# modbrainsv0_3.net
KiCad netlist of a schematic drawn in EAGLE
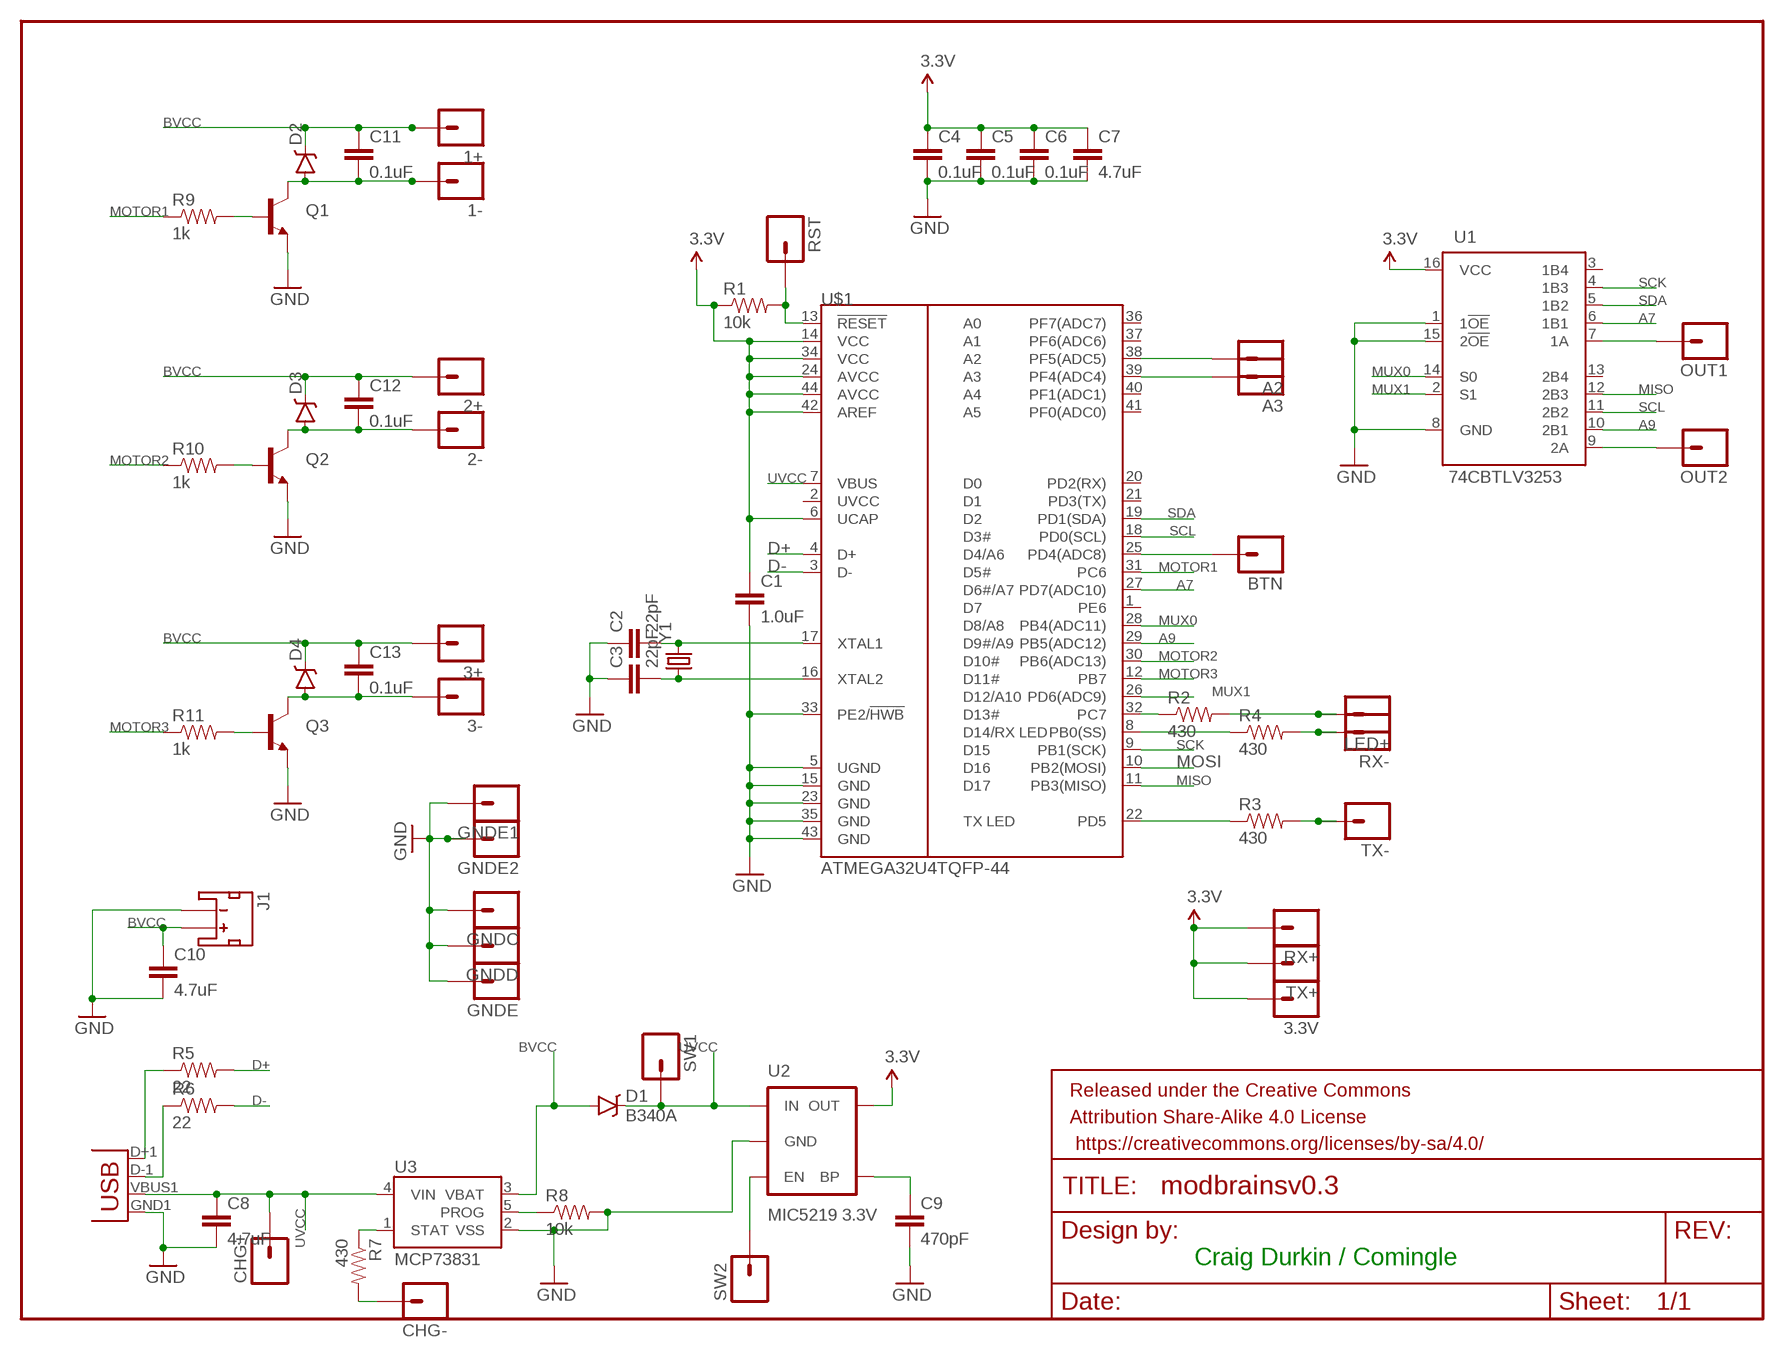
[diagram p0: schematic, sheet 1]

(export (version "E")
  (design (tool "Eeschema 10.0.6"))
  (components
    (comp (ref "1+")
      (value "M01PTH")
      (footprint "eagle-import:1X01")
      (libsource (lib "eagle-import") (part "M01PTH"))
    )
    (comp (ref "1-")
      (value "M01PTH")
      (footprint "eagle-import:1X01")
      (libsource (lib "eagle-import") (part "M01PTH"))
    )
    (comp (ref "2+")
      (value "M01PTH")
      (footprint "eagle-import:1X01")
      (libsource (lib "eagle-import") (part "M01PTH"))
    )
    (comp (ref "2-")
      (value "M01PTH")
      (footprint "eagle-import:1X01")
      (libsource (lib "eagle-import") (part "M01PTH"))
    )
    (comp (ref "3+")
      (value "M01PTH")
      (footprint "eagle-import:1X01")
      (libsource (lib "eagle-import") (part "M01PTH"))
    )
    (comp (ref "3-")
      (value "M01PTH")
      (footprint "eagle-import:1X01")
      (libsource (lib "eagle-import") (part "M01PTH"))
    )
    (comp (ref "3.3V")
      (value "M01PTH")
      (footprint "eagle-import:1X01")
      (libsource (lib "eagle-import") (part "M01PTH"))
    )
    (comp (ref "A2")
      (value "M01PTH")
      (footprint "eagle-import:1X01")
      (libsource (lib "eagle-import") (part "M01PTH"))
    )
    (comp (ref "A3")
      (value "M01PTH")
      (footprint "eagle-import:1X01")
      (libsource (lib "eagle-import") (part "M01PTH"))
    )
    (comp (ref "BTN")
      (value "M01PTH")
      (footprint "eagle-import:1X01")
      (libsource (lib "eagle-import") (part "M01PTH"))
    )
    (comp (ref "C1")
      (value "1.0uF")
      (footprint "eagle-import:0603-CAP")
      (libsource (lib "eagle-import") (part "1.0UF-16V-10%(0603)"))
    )
    (comp (ref "C2")
      (value "22pF")
      (footprint "eagle-import:0603-CAP")
      (libsource (lib "eagle-import") (part "22PF-50V-5%(0603)"))
    )
    (comp (ref "C3")
      (value "22pF")
      (footprint "eagle-import:0603-CAP")
      (libsource (lib "eagle-import") (part "22PF-50V-5%(0603)"))
    )
    (comp (ref "C4")
      (value "0.1uF")
      (footprint "eagle-import:0603-CAP")
      (libsource (lib "eagle-import") (part "CAP0603-CAP"))
    )
    (comp (ref "C5")
      (value "0.1uF")
      (footprint "eagle-import:0603-CAP")
      (libsource (lib "eagle-import") (part "CAP0603-CAP"))
    )
    (comp (ref "C6")
      (value "0.1uF")
      (footprint "eagle-import:0603-CAP")
      (libsource (lib "eagle-import") (part "CAP0603-CAP"))
    )
    (comp (ref "C7")
      (value "4.7uF")
      (footprint "eagle-import:0603-CAP")
      (libsource (lib "eagle-import") (part "CAP0603-CAP"))
    )
    (comp (ref "C8")
      (value "4.7uF")
      (footprint "eagle-import:1206")
      (libsource (lib "eagle-import") (part "CAP1206"))
    )
    (comp (ref "C9")
      (value "470pF")
      (footprint "eagle-import:0603-CAP")
      (libsource (lib "eagle-import") (part "0.1UF-25V(+80/-20%)(0603)"))
    )
    (comp (ref "C10")
      (value "4.7uF")
      (footprint "eagle-import:1206")
      (libsource (lib "eagle-import") (part "CAP1206"))
    )
    (comp (ref "C11")
      (value "0.1uF")
      (footprint "eagle-import:0603-CAP")
      (libsource (lib "eagle-import") (part "0.1UF-25V(+80/-20%)(0603)"))
    )
    (comp (ref "C12")
      (value "0.1uF")
      (footprint "eagle-import:0603-CAP")
      (libsource (lib "eagle-import") (part "0.1UF-25V(+80/-20%)(0603)"))
    )
    (comp (ref "C13")
      (value "0.1uF")
      (footprint "eagle-import:0603-CAP")
      (libsource (lib "eagle-import") (part "0.1UF-25V(+80/-20%)(0603)"))
    )
    (comp (ref "CHG+")
      (value "M01PTH")
      (footprint "eagle-import:1X01")
      (libsource (lib "eagle-import") (part "M01PTH"))
    )
    (comp (ref "CHG-")
      (value "M01PTH")
      (footprint "eagle-import:1X01")
      (libsource (lib "eagle-import") (part "M01PTH"))
    )
    (comp (ref "D1")
      (value "B340A")
      (footprint "eagle-import:SMA-DIODE")
      (libsource (lib "eagle-import") (part "DIODE-SCHOTTKY-B340A"))
    )
    (comp (ref "D2")
      (value "BAT20JFILM")
      (footprint "eagle-import:SOD-323")
      (libsource (lib "eagle-import") (part "BAT20JFILM"))
    )
    (comp (ref "D3")
      (value "BAT20JFILM")
      (footprint "eagle-import:SOD-323")
      (libsource (lib "eagle-import") (part "BAT20JFILM"))
    )
    (comp (ref "D4")
      (value "BAT20JFILM")
      (footprint "eagle-import:SOD-323")
      (libsource (lib "eagle-import") (part "BAT20JFILM"))
    )
    (comp (ref "FRAME1")
      (value "FRAME-LETTER")
      (footprint "eagle-import:CREATIVE_COMMONS")
      (libsource (lib "eagle-import") (part "FRAME-LETTER"))
    )
    (comp (ref "GNDC")
      (value "M01PTH")
      (footprint "eagle-import:1X01")
      (libsource (lib "eagle-import") (part "M01PTH"))
    )
    (comp (ref "GNDD")
      (value "M01PTH")
      (footprint "eagle-import:1X01")
      (libsource (lib "eagle-import") (part "M01PTH"))
    )
    (comp (ref "GNDE")
      (value "M01PTH")
      (footprint "eagle-import:1X01")
      (libsource (lib "eagle-import") (part "M01PTH"))
    )
    (comp (ref "GNDE1")
      (value "M01PTH")
      (footprint "eagle-import:1X01")
      (libsource (lib "eagle-import") (part "M01PTH"))
    )
    (comp (ref "GNDE2")
      (value "M01PTH")
      (footprint "eagle-import:1X01")
      (libsource (lib "eagle-import") (part "M01PTH"))
    )
    (comp (ref "J1")
      (value "JST_2MM_MALE")
      (footprint "eagle-import:JST-2-SMD")
      (libsource (lib "eagle-import") (part "JST_2MM_MALE"))
    )
    (comp (ref "JP4")
      (value "USB")
      (footprint "eagle-import:USB-B-MICRO-SMD_V03")
      (libsource (lib "eagle-import") (part "USB"))
    )
    (comp (ref "LED+")
      (value "M01PTH")
      (footprint "eagle-import:1X01")
      (libsource (lib "eagle-import") (part "M01PTH"))
    )
    (comp (ref "OUT1")
      (value "M01PTH")
      (footprint "eagle-import:1X01")
      (libsource (lib "eagle-import") (part "M01PTH"))
    )
    (comp (ref "OUT2")
      (value "M01PTH")
      (footprint "eagle-import:1X01")
      (libsource (lib "eagle-import") (part "M01PTH"))
    )
    (comp (ref "Q1")
      (value "TRANSISTOR_NPNSOT23-3")
      (footprint "eagle-import:SOT23-3")
      (libsource (lib "eagle-import") (part "TRANSISTOR_NPNSOT23-3"))
    )
    (comp (ref "Q2")
      (value "TRANSISTOR_NPNSOT23-3")
      (footprint "eagle-import:SOT23-3")
      (libsource (lib "eagle-import") (part "TRANSISTOR_NPNSOT23-3"))
    )
    (comp (ref "Q3")
      (value "TRANSISTOR_NPNSOT23-3")
      (footprint "eagle-import:SOT23-3")
      (libsource (lib "eagle-import") (part "TRANSISTOR_NPNSOT23-3"))
    )
    (comp (ref "R1")
      (value "10k")
      (footprint "eagle-import:0603-RES")
      (libsource (lib "eagle-import") (part "RESISTOR0603-RES"))
    )
    (comp (ref "R2")
      (value "430")
      (footprint "eagle-import:0603-RES")
      (libsource (lib "eagle-import") (part "RESISTOR0603"))
    )
    (comp (ref "R3")
      (value "430")
      (footprint "eagle-import:0603-RES")
      (libsource (lib "eagle-import") (part "RESISTOR0603"))
    )
    (comp (ref "R4")
      (value "430")
      (footprint "eagle-import:0603-RES")
      (libsource (lib "eagle-import") (part "RESISTOR0603"))
    )
    (comp (ref "R5")
      (value "22")
      (footprint "eagle-import:0603-RES")
      (libsource (lib "eagle-import") (part "RESISTOR0603-RES"))
    )
    (comp (ref "R6")
      (value "22")
      (footprint "eagle-import:0603-RES")
      (libsource (lib "eagle-import") (part "RESISTOR0603-RES"))
    )
    (comp (ref "R7")
      (value "430")
      (footprint "eagle-import:0603-RES")
      (libsource (lib "eagle-import") (part "RESISTOR0603-RES"))
    )
    (comp (ref "R8")
      (value "10k")
      (footprint "eagle-import:0603-RES")
      (libsource (lib "eagle-import") (part "RESISTOR0603-RES"))
    )
    (comp (ref "R9")
      (value "1k")
      (footprint "eagle-import:0603-RES")
      (libsource (lib "eagle-import") (part "RESISTOR0603-RES"))
    )
    (comp (ref "R10")
      (value "1k")
      (footprint "eagle-import:0603-RES")
      (libsource (lib "eagle-import") (part "RESISTOR0603-RES"))
    )
    (comp (ref "R11")
      (value "1k")
      (footprint "eagle-import:0603-RES")
      (libsource (lib "eagle-import") (part "RESISTOR0603-RES"))
    )
    (comp (ref "RST")
      (value "M01PTH")
      (footprint "eagle-import:1X01")
      (libsource (lib "eagle-import") (part "M01PTH"))
    )
    (comp (ref "RX+")
      (value "M01PTH")
      (footprint "eagle-import:1X01")
      (libsource (lib "eagle-import") (part "M01PTH"))
    )
    (comp (ref "RX-")
      (value "M01PTH")
      (footprint "eagle-import:1X01")
      (libsource (lib "eagle-import") (part "M01PTH"))
    )
    (comp (ref "SW1")
      (value "M01PTH")
      (footprint "eagle-import:1X01")
      (libsource (lib "eagle-import") (part "M01PTH"))
    )
    (comp (ref "SW2")
      (value "M01PTH")
      (footprint "eagle-import:1X01")
      (libsource (lib "eagle-import") (part "M01PTH"))
    )
    (comp (ref "TX+")
      (value "M01PTH")
      (footprint "eagle-import:1X01")
      (libsource (lib "eagle-import") (part "M01PTH"))
    )
    (comp (ref "TX-")
      (value "M01PTH")
      (footprint "eagle-import:1X01")
      (libsource (lib "eagle-import") (part "M01PTH"))
    )
    (comp (ref "U$1")
      (value "ATMEGA32U4TQFP-44")
      (footprint "eagle-import:TQFP44")
      (libsource (lib "eagle-import") (part "ATMEGA32U4TQFP-44"))
    )
    (comp (ref "U1")
      (value "74CBTLV3253")
      (footprint "eagle-import:SSOP16-PRACTICE")
      (libsource (lib "eagle-import") (part "74CBTLV3253"))
    )
    (comp (ref "U2")
      (value "MIC5219 3.3V")
      (footprint "eagle-import:SOT23-5")
      (libsource (lib "eagle-import") (part "V_REG_MIC52193.3V"))
    )
    (comp (ref "U3")
      (value "MCP73831")
      (footprint "eagle-import:SOT23-5")
      (libsource (lib "eagle-import") (part "MCP73831"))
    )
    (comp (ref "Y1")
      (value "CRYSTAL5X3")
      (footprint "eagle-import:CRYSTAL-SMD-5X3")
      (libsource (lib "eagle-import") (part "CRYSTAL5X3"))
    )
  )
  (nets
    (net (code "1") (name "/A7") (class "Default")
      (node (ref "U$1") (pin "27") (pinfunction "PD7(ADC10)_27") (pintype "bidirectional"))
      (node (ref "U1") (pin "6") (pinfunction "1B1_6") (pintype "bidirectional"))
    )
    (net (code "2") (name "/A9") (class "Default")
      (node (ref "U$1") (pin "29") (pinfunction "PB5(ADC12)_29") (pintype "bidirectional"))
      (node (ref "U1") (pin "10") (pinfunction "2B1_10") (pintype "bidirectional"))
    )
    (net (code "3") (name "/BVCC") (class "Default")
      (node (ref "1+") (pin "1") (pinfunction "1_1") (pintype "passive"))
      (node (ref "2+") (pin "1") (pinfunction "1_1") (pintype "passive"))
      (node (ref "3+") (pin "1") (pinfunction "1_1") (pintype "passive"))
      (node (ref "C10") (pin "1") (pinfunction "1_1") (pintype "passive"))
      (node (ref "C11") (pin "1") (pinfunction "1_1") (pintype "passive"))
      (node (ref "C12") (pin "1") (pinfunction "1_1") (pintype "passive"))
      (node (ref "C13") (pin "1") (pinfunction "1_1") (pintype "passive"))
      (node (ref "D1") (pin "A") (pinfunction "A_A") (pintype "passive"))
      (node (ref "D2") (pin "C") (pinfunction "C_C") (pintype "passive"))
      (node (ref "D3") (pin "C") (pinfunction "C_C") (pintype "passive"))
      (node (ref "D4") (pin "C") (pinfunction "C_C") (pintype "passive"))
      (node (ref "J1") (pin "2") (pinfunction "+_2") (pintype "bidirectional"))
      (node (ref "U3") (pin "3") (pinfunction "VBAT_3") (pintype "power_in"))
    )
    (net (code "4") (name "/D+") (class "Default")
      (node (ref "R5") (pin "2") (pinfunction "2_2") (pintype "passive"))
      (node (ref "U$1") (pin "4") (pinfunction "D+_4") (pintype "bidirectional"))
    )
    (net (code "5") (name "/D-") (class "Default")
      (node (ref "R6") (pin "2") (pinfunction "2_2") (pintype "passive"))
      (node (ref "U$1") (pin "3") (pinfunction "D-_3") (pintype "bidirectional"))
    )
    (net (code "6") (name "/MISO") (class "Default")
      (node (ref "U$1") (pin "11") (pinfunction "PB3(MISO)_11") (pintype "bidirectional"))
      (node (ref "U1") (pin "12") (pinfunction "2B3_12") (pintype "bidirectional"))
    )
    (net (code "7") (name "/MOSI") (class "Default")
      (node (ref "U$1") (pin "10") (pinfunction "PB2(MOSI)_10") (pintype "bidirectional"))
    )
    (net (code "8") (name "/MOTOR1") (class "Default")
      (node (ref "R9") (pin "1") (pinfunction "1_1") (pintype "passive"))
      (node (ref "U$1") (pin "31") (pinfunction "PC6_31") (pintype "bidirectional"))
    )
    (net (code "9") (name "/MOTOR2") (class "Default")
      (node (ref "R10") (pin "1") (pinfunction "1_1") (pintype "passive"))
      (node (ref "U$1") (pin "30") (pinfunction "PB6(ADC13)_30") (pintype "bidirectional"))
    )
    (net (code "10") (name "/MOTOR3") (class "Default")
      (node (ref "R11") (pin "1") (pinfunction "1_1") (pintype "passive"))
      (node (ref "U$1") (pin "12") (pinfunction "PB7_12") (pintype "bidirectional"))
    )
    (net (code "11") (name "/MUX0") (class "Default")
      (node (ref "U$1") (pin "28") (pinfunction "PB4(ADC11)_28") (pintype "bidirectional"))
      (node (ref "U1") (pin "14") (pinfunction "S0_14") (pintype "bidirectional"))
    )
    (net (code "12") (name "/MUX1") (class "Default")
      (node (ref "U$1") (pin "26") (pinfunction "PD6(ADC9)_26") (pintype "bidirectional"))
      (node (ref "U1") (pin "2") (pinfunction "S1_2") (pintype "bidirectional"))
    )
    (net (code "13") (name "/SCK") (class "Default")
      (node (ref "U$1") (pin "9") (pinfunction "PB1(SCK)_9") (pintype "bidirectional"))
      (node (ref "U1") (pin "4") (pinfunction "1B3_4") (pintype "bidirectional"))
    )
    (net (code "14") (name "/SCL") (class "Default")
      (node (ref "U$1") (pin "18") (pinfunction "PD0(SCL)_18") (pintype "bidirectional"))
      (node (ref "U1") (pin "11") (pinfunction "2B2_11") (pintype "bidirectional"))
    )
    (net (code "15") (name "/SDA") (class "Default")
      (node (ref "U$1") (pin "19") (pinfunction "PD1(SDA)_19") (pintype "bidirectional"))
      (node (ref "U1") (pin "5") (pinfunction "1B2_5") (pintype "bidirectional"))
    )
    (net (code "16") (name "/UVCC") (class "Default")
      (node (ref "C8") (pin "1") (pinfunction "1_1") (pintype "passive"))
      (node (ref "CHG+") (pin "1") (pinfunction "1_1") (pintype "passive"))
      (node (ref "D1") (pin "C") (pinfunction "C_C") (pintype "passive"))
      (node (ref "JP4") (pin "VBUS1") (pinfunction "VBUS_VBUS1") (pintype "bidirectional"))
      (node (ref "SW1") (pin "1") (pinfunction "1_1") (pintype "passive"))
      (node (ref "U$1") (pin "7") (pinfunction "VBUS_7") (pintype "bidirectional"))
      (node (ref "U2") (pin "1") (pinfunction "IN_1") (pintype "input"))
      (node (ref "U3") (pin "4") (pinfunction "VIN_4") (pintype "power_in"))
    )
    (net (code "17") (name "3.3V") (class "Default")
      (node (ref "3.3V") (pin "1") (pinfunction "1_1") (pintype "passive"))
      (node (ref "C1") (pin "1") (pinfunction "1_1") (pintype "passive"))
      (node (ref "C4") (pin "1") (pinfunction "1_1") (pintype "passive"))
      (node (ref "C5") (pin "1") (pinfunction "1_1") (pintype "passive"))
      (node (ref "C6") (pin "1") (pinfunction "1_1") (pintype "passive"))
      (node (ref "C7") (pin "1") (pinfunction "1_1") (pintype "passive"))
      (node (ref "R1") (pin "1") (pinfunction "1_1") (pintype "passive"))
      (node (ref "RX+") (pin "1") (pinfunction "1_1") (pintype "passive"))
      (node (ref "TX+") (pin "1") (pinfunction "1_1") (pintype "passive"))
      (node (ref "U$1") (pin "14") (pinfunction "VCC_14") (pintype "bidirectional"))
      (node (ref "U$1") (pin "24") (pinfunction "AVCC_24") (pintype "bidirectional"))
      (node (ref "U$1") (pin "34") (pinfunction "VCC_34") (pintype "bidirectional"))
      (node (ref "U$1") (pin "42") (pinfunction "AREF_42") (pintype "bidirectional"))
      (node (ref "U$1") (pin "44") (pinfunction "AVCC_44") (pintype "bidirectional"))
      (node (ref "U$1") (pin "6") (pinfunction "UCAP_6") (pintype "bidirectional"))
      (node (ref "U1") (pin "16") (pinfunction "VCC_16") (pintype "power_in"))
      (node (ref "U2") (pin "5") (pinfunction "OUT_5") (pintype "passive"))
    )
    (net (code "18") (name "GND") (class "Default")
      (node (ref "C1") (pin "2") (pinfunction "2_2") (pintype "passive"))
      (node (ref "C10") (pin "2") (pinfunction "2_2") (pintype "passive"))
      (node (ref "C2") (pin "1") (pinfunction "1_1") (pintype "passive"))
      (node (ref "C3") (pin "1") (pinfunction "1_1") (pintype "passive"))
      (node (ref "C4") (pin "2") (pinfunction "2_2") (pintype "passive"))
      (node (ref "C5") (pin "2") (pinfunction "2_2") (pintype "passive"))
      (node (ref "C6") (pin "2") (pinfunction "2_2") (pintype "passive"))
      (node (ref "C7") (pin "2") (pinfunction "2_2") (pintype "passive"))
      (node (ref "C8") (pin "2") (pinfunction "2_2") (pintype "passive"))
      (node (ref "C9") (pin "2") (pinfunction "2_2") (pintype "passive"))
      (node (ref "GNDC") (pin "1") (pinfunction "1_1") (pintype "passive"))
      (node (ref "GNDD") (pin "1") (pinfunction "1_1") (pintype "passive"))
      (node (ref "GNDE") (pin "1") (pinfunction "1_1") (pintype "passive"))
      (node (ref "GNDE1") (pin "1") (pinfunction "1_1") (pintype "passive"))
      (node (ref "GNDE2") (pin "1") (pinfunction "1_1") (pintype "passive"))
      (node (ref "J1") (pin "1") (pinfunction "-_1") (pintype "bidirectional"))
      (node (ref "JP4") (pin "GND1") (pinfunction "GND_GND1") (pintype "bidirectional"))
      (node (ref "Q1") (pin "2") (pinfunction "E_2") (pintype "passive"))
      (node (ref "Q2") (pin "2") (pinfunction "E_2") (pintype "passive"))
      (node (ref "Q3") (pin "2") (pinfunction "E_2") (pintype "passive"))
      (node (ref "R8") (pin "2") (pinfunction "2_2") (pintype "passive"))
      (node (ref "U$1") (pin "15") (pinfunction "GND_15") (pintype "bidirectional"))
      (node (ref "U$1") (pin "23") (pinfunction "GND_23") (pintype "bidirectional"))
      (node (ref "U$1") (pin "33") (pinfunction "PE2/~{HWB}_33") (pintype "bidirectional"))
      (node (ref "U$1") (pin "35") (pinfunction "GND_35") (pintype "bidirectional"))
      (node (ref "U$1") (pin "43") (pinfunction "GND_43") (pintype "bidirectional"))
      (node (ref "U$1") (pin "5") (pinfunction "UGND_5") (pintype "bidirectional"))
      (node (ref "U1") (pin "1") (pinfunction "1~{OE}_1") (pintype "input"))
      (node (ref "U1") (pin "15") (pinfunction "2~{OE}_15") (pintype "input"))
      (node (ref "U1") (pin "8") (pinfunction "GND_8") (pintype "power_in"))
      (node (ref "U2") (pin "2") (pinfunction "GND_2") (pintype "input"))
      (node (ref "U3") (pin "2") (pinfunction "VSS_2") (pintype "power_in"))
    )
    (net (code "19") (name "Net-(CHG--Pad1)") (class "Default")
      (node (ref "CHG-") (pin "1") (pinfunction "1_1") (pintype "passive"))
      (node (ref "R7") (pin "2") (pinfunction "2_2") (pintype "passive"))
    )
    (net (code "20") (name "Net-(JP4-D+)") (class "Default")
      (node (ref "JP4") (pin "D+1") (pinfunction "D+_D+1") (pintype "bidirectional"))
      (node (ref "R5") (pin "1") (pinfunction "1_1") (pintype "passive"))
    )
    (net (code "21") (name "Net-(JP4-D-)") (class "Default")
      (node (ref "JP4") (pin "D-1") (pinfunction "D-_D-1") (pintype "bidirectional"))
      (node (ref "R6") (pin "1") (pinfunction "1_1") (pintype "passive"))
    )
    (net (code "22") (name "Net-(LED+-Pad1)") (class "Default")
      (node (ref "LED+") (pin "1") (pinfunction "1_1") (pintype "passive"))
      (node (ref "R2") (pin "2") (pinfunction "2_2") (pintype "passive"))
    )
    (net (code "23") (name "Net-(Q1-B)") (class "Default")
      (node (ref "Q1") (pin "1") (pinfunction "B_1") (pintype "passive"))
      (node (ref "R9") (pin "2") (pinfunction "2_2") (pintype "passive"))
    )
    (net (code "24") (name "Net-(Q1-C)") (class "Default")
      (node (ref "1-") (pin "1") (pinfunction "1_1") (pintype "passive"))
      (node (ref "C11") (pin "2") (pinfunction "2_2") (pintype "passive"))
      (node (ref "D2") (pin "A") (pinfunction "A_A") (pintype "passive"))
      (node (ref "Q1") (pin "3") (pinfunction "C_3") (pintype "passive"))
    )
    (net (code "25") (name "Net-(Q2-B)") (class "Default")
      (node (ref "Q2") (pin "1") (pinfunction "B_1") (pintype "passive"))
      (node (ref "R10") (pin "2") (pinfunction "2_2") (pintype "passive"))
    )
    (net (code "26") (name "Net-(Q2-C)") (class "Default")
      (node (ref "2-") (pin "1") (pinfunction "1_1") (pintype "passive"))
      (node (ref "C12") (pin "2") (pinfunction "2_2") (pintype "passive"))
      (node (ref "D3") (pin "A") (pinfunction "A_A") (pintype "passive"))
      (node (ref "Q2") (pin "3") (pinfunction "C_3") (pintype "passive"))
    )
    (net (code "27") (name "Net-(Q3-B)") (class "Default")
      (node (ref "Q3") (pin "1") (pinfunction "B_1") (pintype "passive"))
      (node (ref "R11") (pin "2") (pinfunction "2_2") (pintype "passive"))
    )
    (net (code "28") (name "Net-(Q3-C)") (class "Default")
      (node (ref "3-") (pin "1") (pinfunction "1_1") (pintype "passive"))
      (node (ref "C13") (pin "2") (pinfunction "2_2") (pintype "passive"))
      (node (ref "D4") (pin "A") (pinfunction "A_A") (pintype "passive"))
      (node (ref "Q3") (pin "3") (pinfunction "C_3") (pintype "passive"))
    )
    (net (code "29") (name "Net-(R3-Pad2)") (class "Default")
      (node (ref "R3") (pin "2") (pinfunction "2_2") (pintype "passive"))
      (node (ref "TX-") (pin "1") (pinfunction "1_1") (pintype "passive"))
    )
    (net (code "30") (name "Net-(R4-Pad2)") (class "Default")
      (node (ref "R4") (pin "2") (pinfunction "2_2") (pintype "passive"))
      (node (ref "RX-") (pin "1") (pinfunction "1_1") (pintype "passive"))
    )
    (net (code "31") (name "Net-(U$1-PB0(SS))") (class "Default")
      (node (ref "R4") (pin "1") (pinfunction "1_1") (pintype "passive"))
      (node (ref "U$1") (pin "8") (pinfunction "PB0(SS)_8") (pintype "bidirectional"))
    )
    (net (code "32") (name "Net-(U$1-PC7)") (class "Default")
      (node (ref "R2") (pin "1") (pinfunction "1_1") (pintype "passive"))
      (node (ref "U$1") (pin "32") (pinfunction "PC7_32") (pintype "bidirectional"))
    )
    (net (code "33") (name "Net-(U$1-PD4(ADC8))") (class "Default")
      (node (ref "BTN") (pin "1") (pinfunction "1_1") (pintype "passive"))
      (node (ref "U$1") (pin "25") (pinfunction "PD4(ADC8)_25") (pintype "bidirectional"))
    )
    (net (code "34") (name "Net-(U$1-PD5)") (class "Default")
      (node (ref "R3") (pin "1") (pinfunction "1_1") (pintype "passive"))
      (node (ref "U$1") (pin "22") (pinfunction "PD5_22") (pintype "bidirectional"))
    )
    (net (code "35") (name "Net-(U$1-PF4(ADC4))") (class "Default")
      (node (ref "A3") (pin "1") (pinfunction "1_1") (pintype "passive"))
      (node (ref "U$1") (pin "39") (pinfunction "PF4(ADC4)_39") (pintype "bidirectional"))
    )
    (net (code "36") (name "Net-(U$1-PF5(ADC5))") (class "Default")
      (node (ref "A2") (pin "1") (pinfunction "1_1") (pintype "passive"))
      (node (ref "U$1") (pin "38") (pinfunction "PF5(ADC5)_38") (pintype "bidirectional"))
    )
    (net (code "37") (name "Net-(U$1-XTAL1)") (class "Default")
      (node (ref "C2") (pin "2") (pinfunction "2_2") (pintype "passive"))
      (node (ref "U$1") (pin "17") (pinfunction "XTAL1_17") (pintype "bidirectional"))
      (node (ref "Y1") (pin "3") (pinfunction "2_3") (pintype "passive"))
    )
    (net (code "38") (name "Net-(U$1-XTAL2)") (class "Default")
      (node (ref "C3") (pin "2") (pinfunction "2_2") (pintype "passive"))
      (node (ref "U$1") (pin "16") (pinfunction "XTAL2_16") (pintype "bidirectional"))
      (node (ref "Y1") (pin "1") (pinfunction "1_1") (pintype "passive"))
    )
    (net (code "39") (name "Net-(U$1-~{RESET})") (class "Default")
      (node (ref "R1") (pin "2") (pinfunction "2_2") (pintype "passive"))
      (node (ref "RST") (pin "1") (pinfunction "1_1") (pintype "passive"))
      (node (ref "U$1") (pin "13") (pinfunction "~{RESET}_13") (pintype "bidirectional"))
    )
    (net (code "40") (name "Net-(U1-1A)") (class "Default")
      (node (ref "OUT1") (pin "1") (pinfunction "1_1") (pintype "passive"))
      (node (ref "U1") (pin "7") (pinfunction "1A_7") (pintype "bidirectional"))
    )
    (net (code "41") (name "Net-(U1-2A)") (class "Default")
      (node (ref "OUT2") (pin "1") (pinfunction "1_1") (pintype "passive"))
      (node (ref "U1") (pin "9") (pinfunction "2A_9") (pintype "bidirectional"))
    )
    (net (code "42") (name "Net-(U2-BP)") (class "Default")
      (node (ref "C9") (pin "1") (pinfunction "1_1") (pintype "passive"))
      (node (ref "U2") (pin "4") (pinfunction "BP_4") (pintype "input"))
    )
    (net (code "43") (name "Net-(U2-EN)") (class "Default")
      (node (ref "SW2") (pin "1") (pinfunction "1_1") (pintype "passive"))
      (node (ref "U2") (pin "3") (pinfunction "EN_3") (pintype "input"))
    )
    (net (code "44") (name "Net-(U3-PROG)") (class "Default")
      (node (ref "R8") (pin "1") (pinfunction "1_1") (pintype "passive"))
      (node (ref "U3") (pin "5") (pinfunction "PROG_5") (pintype "bidirectional"))
    )
    (net (code "45") (name "Net-(U3-STAT)") (class "Default")
      (node (ref "R7") (pin "1") (pinfunction "1_1") (pintype "passive"))
      (node (ref "U3") (pin "1") (pinfunction "STAT_1") (pintype "output"))
    )
    (net (code "46") (name "unconnected-(J1-PAD1-PadNC1)") (class "Default")
      (node (ref "J1") (pin "NC1") (pinfunction "PAD1_NC1") (pintype "bidirectional"))
    )
    (net (code "47") (name "unconnected-(J1-PAD2-PadNC2)") (class "Default")
      (node (ref "J1") (pin "NC2") (pinfunction "PAD2_NC2") (pintype "bidirectional"))
    )
    (net (code "48") (name "unconnected-(U$1-PD2(RX)-Pad20)") (class "Default")
      (node (ref "U$1") (pin "20") (pinfunction "PD2(RX)_20") (pintype "bidirectional"))
    )
    (net (code "49") (name "unconnected-(U$1-PD3(TX)-Pad21)") (class "Default")
      (node (ref "U$1") (pin "21") (pinfunction "PD3(TX)_21") (pintype "bidirectional"))
    )
    (net (code "50") (name "unconnected-(U$1-PE6-Pad1)") (class "Default")
      (node (ref "U$1") (pin "1") (pinfunction "PE6_1") (pintype "bidirectional"))
    )
    (net (code "51") (name "unconnected-(U$1-PF0(ADC0)-Pad41)") (class "Default")
      (node (ref "U$1") (pin "41") (pinfunction "PF0(ADC0)_41") (pintype "bidirectional"))
    )
    (net (code "52") (name "unconnected-(U$1-PF1(ADC1)-Pad40)") (class "Default")
      (node (ref "U$1") (pin "40") (pinfunction "PF1(ADC1)_40") (pintype "bidirectional"))
    )
    (net (code "53") (name "unconnected-(U$1-PF6(ADC6)-Pad37)") (class "Default")
      (node (ref "U$1") (pin "37") (pinfunction "PF6(ADC6)_37") (pintype "bidirectional"))
    )
    (net (code "54") (name "unconnected-(U$1-PF7(ADC7)-Pad36)") (class "Default")
      (node (ref "U$1") (pin "36") (pinfunction "PF7(ADC7)_36") (pintype "bidirectional"))
    )
    (net (code "55") (name "unconnected-(U$1-UVCC-Pad2)") (class "Default")
      (node (ref "U$1") (pin "2") (pinfunction "UVCC_2") (pintype "bidirectional"))
    )
    (net (code "56") (name "unconnected-(U1-1B4-Pad3)") (class "Default")
      (node (ref "U1") (pin "3") (pinfunction "1B4_3") (pintype "bidirectional"))
    )
    (net (code "57") (name "unconnected-(U1-2B4-Pad13)") (class "Default")
      (node (ref "U1") (pin "13") (pinfunction "2B4_13") (pintype "bidirectional"))
    )
  )
)
